# TouScruino-v1.net
KiCad netlist of a schematic drawn in EAGLE
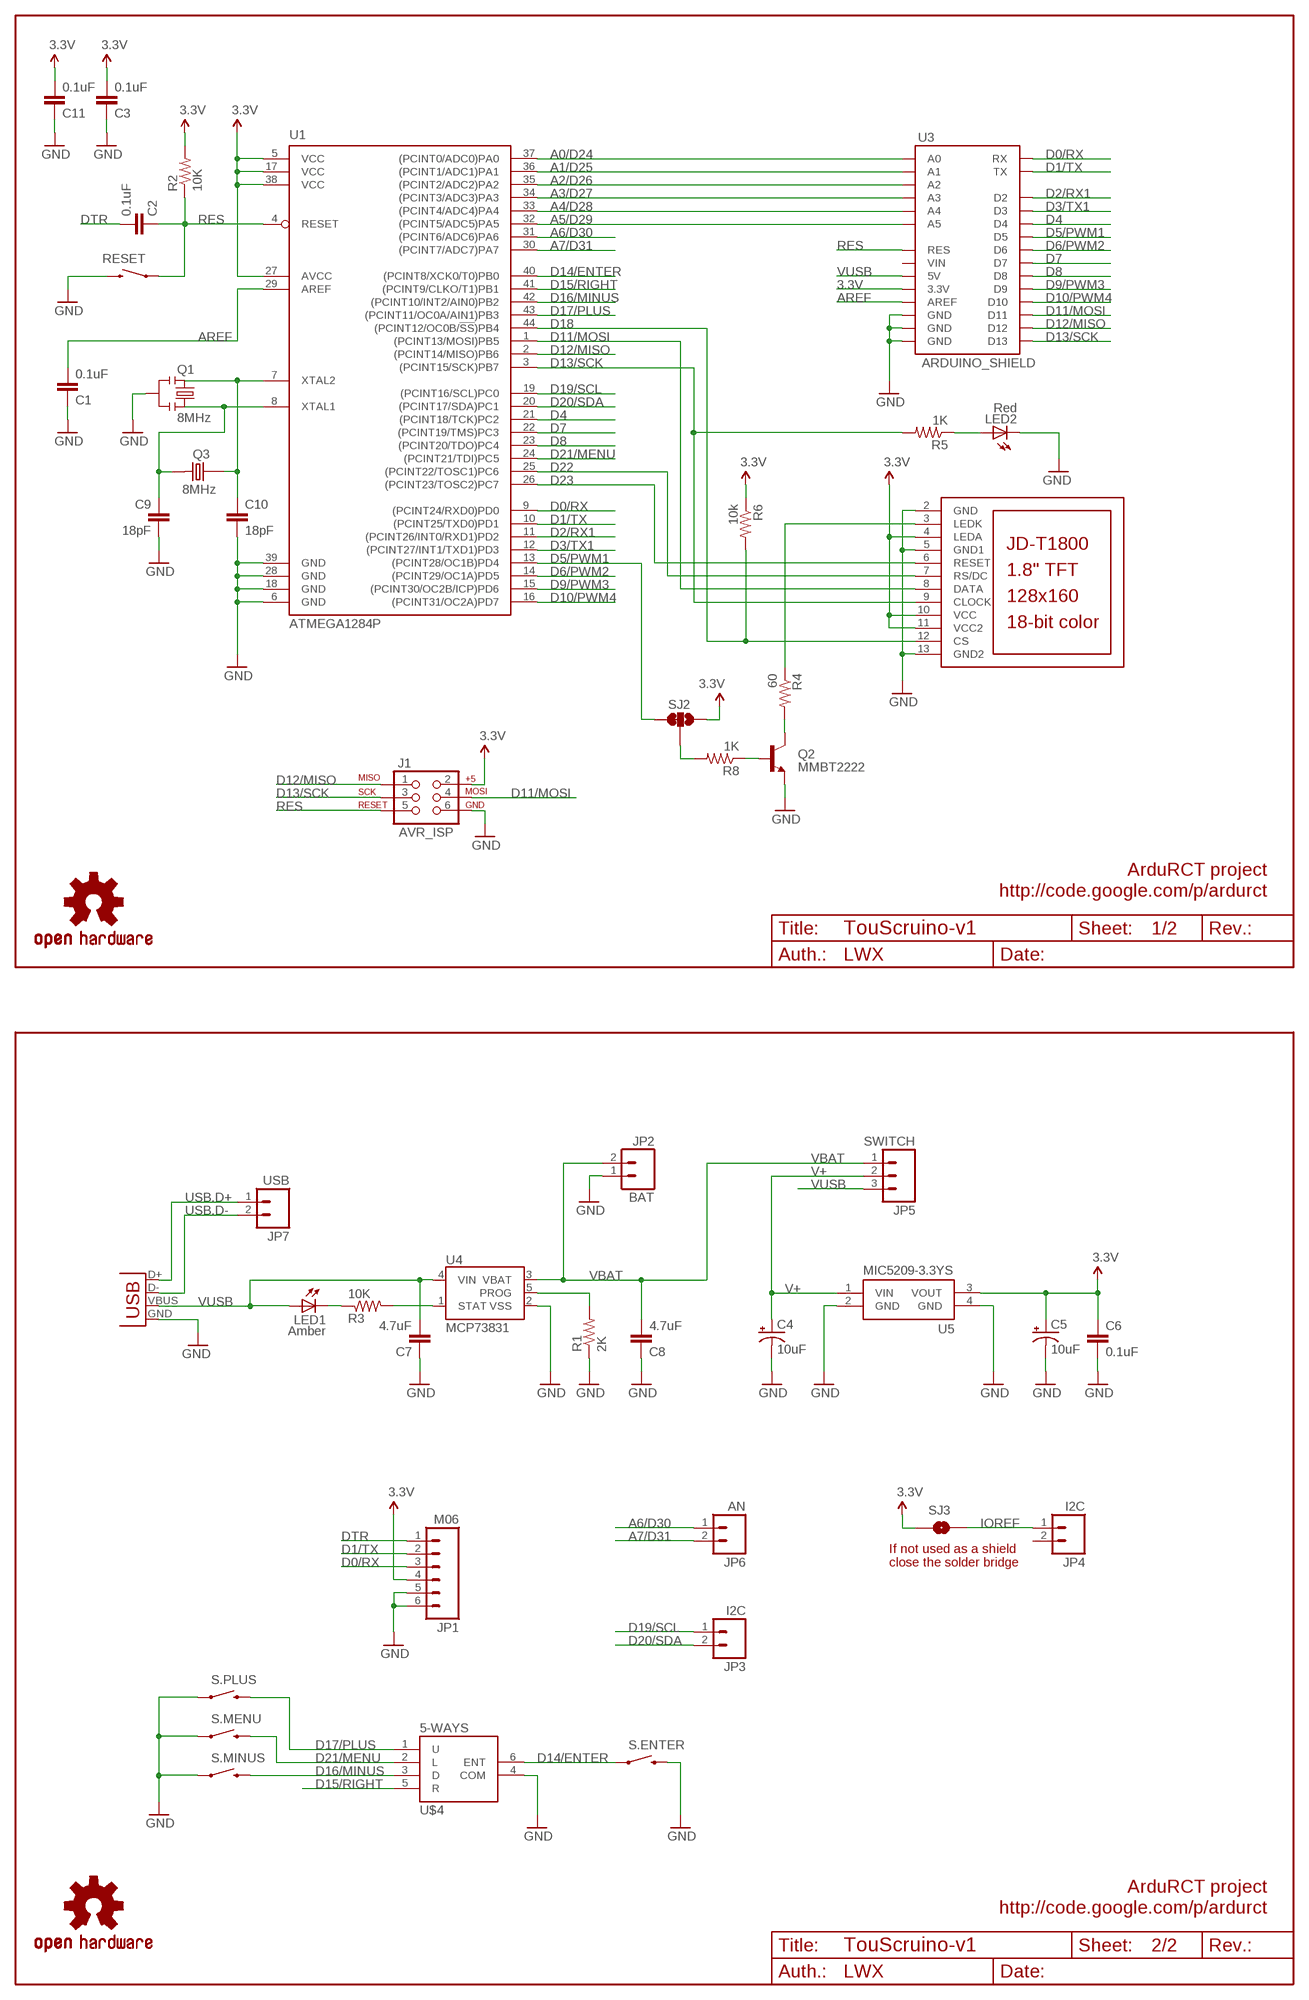
[diagram p0: schematic, sheet 1]

(export (version "E")
  (design (tool "Eeschema 10.0.6"))
  (components
    (comp (ref "C1")
      (value "0.1uF")
      (footprint "eagle-import:0805")
      (libsource (lib "eagle-import") (part "CAP0805"))
    )
    (comp (ref "C2")
      (value "0.1uF")
      (footprint "eagle-import:0805")
      (libsource (lib "eagle-import") (part "CAP0805"))
    )
    (comp (ref "C3")
      (value "0.1uF")
      (footprint "eagle-import:0805")
      (libsource (lib "eagle-import") (part "CAP0805"))
    )
    (comp (ref "C4")
      (value "10uF")
      (footprint "eagle-import:EIA3216")
      (libsource (lib "eagle-import") (part "CAP_POL1206"))
    )
    (comp (ref "C5")
      (value "10uF")
      (footprint "eagle-import:EIA3216")
      (libsource (lib "eagle-import") (part "CAP_POL1206"))
    )
    (comp (ref "C6")
      (value "0.1uF")
      (footprint "eagle-import:0805")
      (libsource (lib "eagle-import") (part "CAP0805"))
    )
    (comp (ref "C7")
      (value "4.7uF")
      (footprint "eagle-import:0805")
      (libsource (lib "eagle-import") (part "CAP0805"))
    )
    (comp (ref "C8")
      (value "4.7uF")
      (footprint "eagle-import:0805")
      (libsource (lib "eagle-import") (part "CAP0805"))
    )
    (comp (ref "C9")
      (value "18pF")
      (footprint "eagle-import:0603-CAP")
      (libsource (lib "eagle-import") (part "CAP0603-CAP"))
    )
    (comp (ref "C10")
      (value "18pF")
      (footprint "eagle-import:0603-CAP")
      (libsource (lib "eagle-import") (part "CAP0603-CAP"))
    )
    (comp (ref "C11")
      (value "0.1uF")
      (footprint "eagle-import:0805")
      (libsource (lib "eagle-import") (part "CAP0805"))
    )
    (comp (ref "J1")
      (value "AVR_ISP")
      (footprint "eagle-import:2X3")
      (libsource (lib "eagle-import") (part "AVR_SPI_PRG_6PTH"))
    )
    (comp (ref "JP1")
      (value "M06")
      (footprint "eagle-import:1X06")
      (libsource (lib "eagle-import") (part "M06"))
    )
    (comp (ref "JP2")
      (value "BAT")
      (footprint "eagle-import:JST-2-SMD")
      (libsource (lib "eagle-import") (part "M02-JST-2MM-SMT"))
    )
    (comp (ref "JP3")
      (value "I2C")
      (footprint "eagle-import:1X02")
      (libsource (lib "eagle-import") (part "M02"))
    )
    (comp (ref "JP4")
      (value "I2C")
      (footprint "eagle-import:1X02")
      (libsource (lib "eagle-import") (part "M02"))
    )
    (comp (ref "JP5")
      (value "SWITCH")
      (footprint "eagle-import:1X3_LONGPAD")
      (libsource (lib "eagle-import") (part "M03"))
    )
    (comp (ref "JP6")
      (value "AN")
      (footprint "eagle-import:1X02")
      (libsource (lib "eagle-import") (part "M02"))
    )
    (comp (ref "JP7")
      (value "USB")
      (footprint "eagle-import:1X02")
      (libsource (lib "eagle-import") (part "M02"))
    )
    (comp (ref "LCD1")
      (value "JD-T1800")
      (footprint "eagle-import:JD-T1800")
      (libsource (lib "eagle-import") (part "JD-T1800"))
    )
    (comp (ref "LED1")
      (value "Amber")
      (footprint "eagle-import:LED")
      (libsource (lib "eagle-import") (part "LED"))
    )
    (comp (ref "LED2")
      (value "Red")
      (footprint "eagle-import:LED-0805")
      (libsource (lib "eagle-import") (part "LED805"))
    )
    (comp (ref "Q1")
      (value "8MHz")
      (footprint "eagle-import:RESONATOR-SMD")
      (libsource (lib "eagle-import") (part "RESONATORSMD"))
    )
    (comp (ref "Q2")
      (value "MMBT2222")
      (footprint "eagle-import:SOT23-3")
      (libsource (lib "eagle-import") (part "TRANSISTOR_NPNSOT23-3"))
    )
    (comp (ref "Q3")
      (value "8MHz")
      (footprint "eagle-import:CRYSTAL_5X3.2")
      (libsource (lib "eagle-import") (part "CRYSTAL_5X3.2"))
    )
    (comp (ref "R1")
      (value "2K")
      (footprint "eagle-import:0805")
      (libsource (lib "eagle-import") (part "RESISTOR0805-RES"))
    )
    (comp (ref "R2")
      (value "10K")
      (footprint "eagle-import:0805")
      (libsource (lib "eagle-import") (part "RESISTOR0805-RES"))
    )
    (comp (ref "R3")
      (value "10K")
      (footprint "eagle-import:0805")
      (libsource (lib "eagle-import") (part "RESISTOR0805-RES"))
    )
    (comp (ref "R4")
      (value "60")
      (footprint "eagle-import:0805")
      (libsource (lib "eagle-import") (part "RESISTOR0805-RES"))
    )
    (comp (ref "R5")
      (value "1K")
      (footprint "eagle-import:0805")
      (libsource (lib "eagle-import") (part "RESISTOR0805-RES"))
    )
    (comp (ref "R6")
      (value "10k")
      (footprint "eagle-import:0805")
      (libsource (lib "eagle-import") (part "RESISTOR0805-RES"))
    )
    (comp (ref "R8")
      (value "1K")
      (footprint "eagle-import:0805")
      (libsource (lib "eagle-import") (part "RESISTOR0805-RES"))
    )
    (comp (ref "RESET")
      (value "SWITCH-MOMENTARY-2SMD")
      (footprint "eagle-import:TACTILE_SWITCH_SMD")
      (libsource (lib "eagle-import") (part "SWITCH-MOMENTARY-2SMD"))
    )
    (comp (ref "S.ENTER")
      (value "SWITCH_SMD")
      (footprint "eagle-import:TACTILE_SWITCH_SMD")
      (libsource (lib "eagle-import") (part "SWITCH_SMD"))
    )
    (comp (ref "S.MENU")
      (value "SWITCH_SMD")
      (footprint "eagle-import:TACTILE_SWITCH_SMD")
      (libsource (lib "eagle-import") (part "SWITCH_SMD"))
    )
    (comp (ref "S.MINUS")
      (value "SWITCH_SMD")
      (footprint "eagle-import:TACTILE_SWITCH_SMD")
      (libsource (lib "eagle-import") (part "SWITCH_SMD"))
    )
    (comp (ref "S.PLUS")
      (value "SWITCH_SMD")
      (footprint "eagle-import:TACTILE_SWITCH_SMD")
      (libsource (lib "eagle-import") (part "SWITCH_SMD"))
    )
    (comp (ref "SJ2")
      (value "SJ_2WAYS_1-2")
      (footprint "eagle-import:SJ_2WAYS_1-2_S")
      (libsource (lib "eagle-import") (part "SJ_2WAYS_1-2"))
    )
    (comp (ref "SJ3")
      (value "SOLDERJUMPERNO")
      (footprint "eagle-import:SJ_2S-NO")
      (libsource (lib "eagle-import") (part "SOLDERJUMPERNO"))
    )
    (comp (ref "U$3")
      (value "OSHW-LOGOM")
      (footprint "eagle-import:OSHW-LOGO-M")
      (libsource (lib "eagle-import") (part "OSHW-LOGOM"))
    )
    (comp (ref "U$4")
      (value "5-WAYS")
      (footprint "eagle-import:5-WAYS_ALPS")
      (libsource (lib "eagle-import") (part "5-WAYS"))
    )
    (comp (ref "U$5")
      (value "OSHW-LOGOM")
      (footprint "eagle-import:OSHW-LOGO-M")
      (libsource (lib "eagle-import") (part "OSHW-LOGOM"))
    )
    (comp (ref "U1")
      (value "ATMEGA1284P")
      (footprint "eagle-import:TQFP44")
      (libsource (lib "eagle-import") (part "ATMEGA324A"))
    )
    (comp (ref "U3")
      (value "ARDUINO_SHIELD")
      (footprint "eagle-import:ARDUINO_SHIELD")
      (libsource (lib "eagle-import") (part "ARDUINO_SHIELD"))
    )
    (comp (ref "U4")
      (value "MCP73831")
      (footprint "eagle-import:SOT23-5")
      (libsource (lib "eagle-import") (part "MCP73831"))
    )
    (comp (ref "U5")
      (value "MIC5209-3.3YS")
      (footprint "eagle-import:SOT223")
      (libsource (lib "eagle-import") (part "MIC5209"))
    )
    (comp (ref "X1")
      (value "USBSMD")
      (footprint "eagle-import:USB-MINIB")
      (libsource (lib "eagle-import") (part "USBSMD"))
    )
  )
  (nets
    (net (code "1") (name "/A0{slash}D24") (class "Default")
      (node (ref "U1") (pin "37") (pinfunction "(PCINT0/ADC0)PA0_37") (pintype "bidirectional"))
      (node (ref "U3") (pin "A0") (pinfunction "A0_A0") (pintype "bidirectional"))
    )
    (net (code "2") (name "/A1{slash}D25") (class "Default")
      (node (ref "U1") (pin "36") (pinfunction "(PCINT1/ADC1)PA1_36") (pintype "bidirectional"))
      (node (ref "U3") (pin "A1") (pinfunction "A1_A1") (pintype "bidirectional"))
    )
    (net (code "3") (name "/A2{slash}D26") (class "Default")
      (node (ref "U1") (pin "35") (pinfunction "(PCINT2/ADC2)PA2_35") (pintype "bidirectional"))
      (node (ref "U3") (pin "A2") (pinfunction "A2_A2") (pintype "bidirectional"))
    )
    (net (code "4") (name "/A3{slash}D27") (class "Default")
      (node (ref "U1") (pin "34") (pinfunction "(PCINT3/ADC3)PA3_34") (pintype "bidirectional"))
      (node (ref "U3") (pin "A3") (pinfunction "A3_A3") (pintype "bidirectional"))
    )
    (net (code "5") (name "/A4{slash}D28") (class "Default")
      (node (ref "U1") (pin "33") (pinfunction "(PCINT4/ADC4)PA4_33") (pintype "bidirectional"))
      (node (ref "U3") (pin "A4") (pinfunction "A4_A4") (pintype "bidirectional"))
    )
    (net (code "6") (name "/A5{slash}D29") (class "Default")
      (node (ref "U1") (pin "32") (pinfunction "(PCINT5/ADC5)PA5_32") (pintype "bidirectional"))
      (node (ref "U3") (pin "A5") (pinfunction "A5_A5") (pintype "bidirectional"))
    )
    (net (code "7") (name "/A6{slash}D30") (class "Default")
      (node (ref "JP6") (pin "1") (pinfunction "1_1") (pintype "passive"))
      (node (ref "U1") (pin "31") (pinfunction "(PCINT6/ADC6)PA6_31") (pintype "bidirectional"))
    )
    (net (code "8") (name "/A7{slash}D31") (class "Default")
      (node (ref "JP6") (pin "2") (pinfunction "2_2") (pintype "passive"))
      (node (ref "U1") (pin "30") (pinfunction "(PCINT7/ADC7)PA7_30") (pintype "bidirectional"))
    )
    (net (code "9") (name "/AREF") (class "Default")
      (node (ref "C1") (pin "2") (pinfunction "2_2") (pintype "passive"))
      (node (ref "U1") (pin "29") (pinfunction "AREF_29") (pintype "passive"))
      (node (ref "U3") (pin "AREF") (pinfunction "AREF_AREF") (pintype "bidirectional"))
    )
    (net (code "10") (name "/D0{slash}RX") (class "Default")
      (node (ref "JP1") (pin "3") (pinfunction "3_3") (pintype "passive"))
      (node (ref "U1") (pin "9") (pinfunction "(PCINT24/RXD0)PD0_9") (pintype "bidirectional"))
      (node (ref "U3") (pin "RX") (pinfunction "RX_RX") (pintype "bidirectional"))
    )
    (net (code "11") (name "/D1{slash}TX") (class "Default")
      (node (ref "JP1") (pin "2") (pinfunction "2_2") (pintype "passive"))
      (node (ref "U1") (pin "10") (pinfunction "(PCINT25/TXD0)PD1_10") (pintype "bidirectional"))
      (node (ref "U3") (pin "TX") (pinfunction "TX_TX") (pintype "bidirectional"))
    )
    (net (code "12") (name "/D2{slash}RX1") (class "Default")
      (node (ref "U1") (pin "11") (pinfunction "(PCINT26/INT0/RXD1)PD2_11") (pintype "bidirectional"))
      (node (ref "U3") (pin "D2") (pinfunction "D2_D2") (pintype "bidirectional"))
    )
    (net (code "13") (name "/D3{slash}TX1") (class "Default")
      (node (ref "U1") (pin "12") (pinfunction "(PCINT27/INT1/TXD1)PD3_12") (pintype "bidirectional"))
      (node (ref "U3") (pin "D3") (pinfunction "D3_D3") (pintype "bidirectional"))
    )
    (net (code "14") (name "/D4") (class "Default")
      (node (ref "U1") (pin "21") (pinfunction "(PCINT18/TCK)PC2_21") (pintype "output"))
      (node (ref "U3") (pin "D4") (pinfunction "D4_D4") (pintype "bidirectional"))
    )
    (net (code "15") (name "/D5{slash}PWM1") (class "Default")
      (node (ref "SJ2") (pin "1") (pinfunction "1_1") (pintype "passive"))
      (node (ref "U1") (pin "13") (pinfunction "(PCINT28/OC1B)PD4_13") (pintype "bidirectional"))
      (node (ref "U3") (pin "D5") (pinfunction "D5_D5") (pintype "bidirectional"))
    )
    (net (code "16") (name "/D6{slash}PWM2") (class "Default")
      (node (ref "U1") (pin "14") (pinfunction "(PCINT29/OC1A)PD5_14") (pintype "bidirectional"))
      (node (ref "U3") (pin "D6") (pinfunction "D6_D6") (pintype "bidirectional"))
    )
    (net (code "17") (name "/D7") (class "Default")
      (node (ref "U1") (pin "22") (pinfunction "(PCINT19/TMS)PC3_22") (pintype "output"))
      (node (ref "U3") (pin "D7") (pinfunction "D7_D7") (pintype "bidirectional"))
    )
    (net (code "18") (name "/D8") (class "Default")
      (node (ref "U1") (pin "23") (pinfunction "(PCINT20/TDO)PC4_23") (pintype "output"))
      (node (ref "U3") (pin "D8") (pinfunction "D8_D8") (pintype "bidirectional"))
    )
    (net (code "19") (name "/D9{slash}PWM3") (class "Default")
      (node (ref "U1") (pin "15") (pinfunction "(PCINT30/OC2B/ICP)PD6_15") (pintype "bidirectional"))
      (node (ref "U3") (pin "D9") (pinfunction "D9_D9") (pintype "bidirectional"))
    )
    (net (code "20") (name "/D10{slash}PWM4") (class "Default")
      (node (ref "U1") (pin "16") (pinfunction "(PCINT31/OC2A)PD7_16") (pintype "bidirectional"))
      (node (ref "U3") (pin "D10") (pinfunction "D10_D10") (pintype "bidirectional"))
    )
    (net (code "21") (name "/D11{slash}MOSI") (class "Default")
      (node (ref "J1") (pin "4") (pinfunction "4_4") (pintype "passive"))
      (node (ref "LCD1") (pin "8") (pinfunction "DATA_8") (pintype "bidirectional"))
      (node (ref "U1") (pin "1") (pinfunction "(PCINT13/MOSI)PB5_1") (pintype "bidirectional"))
      (node (ref "U3") (pin "D11") (pinfunction "D11_D11") (pintype "bidirectional"))
    )
    (net (code "22") (name "/D12{slash}MISO") (class "Default")
      (node (ref "J1") (pin "1") (pinfunction "1_1") (pintype "passive"))
      (node (ref "U1") (pin "2") (pinfunction "(PCINT14/MISO)PB6_2") (pintype "bidirectional"))
      (node (ref "U3") (pin "D12") (pinfunction "D12_D12") (pintype "bidirectional"))
    )
    (net (code "23") (name "/D13{slash}SCK") (class "Default")
      (node (ref "J1") (pin "3") (pinfunction "3_3") (pintype "passive"))
      (node (ref "LCD1") (pin "9") (pinfunction "CLOCK_9") (pintype "input"))
      (node (ref "R5") (pin "2") (pinfunction "2_2") (pintype "passive"))
      (node (ref "U1") (pin "3") (pinfunction "(PCINT15/SCK)PB7_3") (pintype "bidirectional"))
      (node (ref "U3") (pin "D13") (pinfunction "D13_D13") (pintype "bidirectional"))
    )
    (net (code "24") (name "/D14{slash}ENTER") (class "Default")
      (node (ref "S.ENTER") (pin "1") (pinfunction "1_1") (pintype "passive"))
      (node (ref "U$4") (pin "6") (pinfunction "ENT_6") (pintype "bidirectional"))
      (node (ref "U1") (pin "40") (pinfunction "(PCINT8/XCK0/T0)PB0_40") (pintype "bidirectional"))
    )
    (net (code "25") (name "/D15{slash}RIGHT") (class "Default")
      (node (ref "U$4") (pin "5") (pinfunction "R_5") (pintype "bidirectional"))
      (node (ref "U1") (pin "41") (pinfunction "(PCINT9/CLKO/T1)PB1_41") (pintype "bidirectional"))
    )
    (net (code "26") (name "/D16{slash}MINUS") (class "Default")
      (node (ref "S.MINUS") (pin "3") (pinfunction "2_3") (pintype "passive"))
      (node (ref "U$4") (pin "3") (pinfunction "D_3") (pintype "bidirectional"))
      (node (ref "U1") (pin "42") (pinfunction "(PCINT10/INT2/AIN0)PB2_42") (pintype "bidirectional"))
    )
    (net (code "27") (name "/D17{slash}PLUS") (class "Default")
      (node (ref "S.PLUS") (pin "3") (pinfunction "2_3") (pintype "passive"))
      (node (ref "U$4") (pin "1") (pinfunction "U_1") (pintype "bidirectional"))
      (node (ref "U1") (pin "43") (pinfunction "(PCINT11/OC0A/AIN1)PB3_43") (pintype "bidirectional"))
    )
    (net (code "28") (name "/D18") (class "Default")
      (node (ref "LCD1") (pin "12") (pinfunction "CS_12") (pintype "input"))
      (node (ref "R6") (pin "2") (pinfunction "2_2") (pintype "passive"))
      (node (ref "U1") (pin "44") (pinfunction "(PCINT12/OC0B/~{SS})PB4_44") (pintype "bidirectional"))
    )
    (net (code "29") (name "/D19{slash}SCL") (class "Default")
      (node (ref "JP3") (pin "1") (pinfunction "1_1") (pintype "passive"))
      (node (ref "U1") (pin "19") (pinfunction "(PCINT16/SCL)PC0_19") (pintype "output"))
    )
    (net (code "30") (name "/D20{slash}SDA") (class "Default")
      (node (ref "JP3") (pin "2") (pinfunction "2_2") (pintype "passive"))
      (node (ref "U1") (pin "20") (pinfunction "(PCINT17/SDA)PC1_20") (pintype "output"))
    )
    (net (code "31") (name "/D21{slash}MENU") (class "Default")
      (node (ref "S.MENU") (pin "3") (pinfunction "2_3") (pintype "passive"))
      (node (ref "U$4") (pin "2") (pinfunction "L_2") (pintype "bidirectional"))
      (node (ref "U1") (pin "24") (pinfunction "(PCINT21/TDI)PC5_24") (pintype "output"))
    )
    (net (code "32") (name "/D22") (class "Default")
      (node (ref "LCD1") (pin "7") (pinfunction "RS/DC_7") (pintype "input"))
      (node (ref "U1") (pin "25") (pinfunction "(PCINT22/TOSC1)PC6_25") (pintype "output"))
    )
    (net (code "33") (name "/D23") (class "Default")
      (node (ref "LCD1") (pin "6") (pinfunction "RESET_6") (pintype "input"))
      (node (ref "U1") (pin "26") (pinfunction "(PCINT23/TOSC2)PC7_26") (pintype "output"))
    )
    (net (code "34") (name "/DTR") (class "Default")
      (node (ref "C2") (pin "2") (pinfunction "2_2") (pintype "passive"))
      (node (ref "JP1") (pin "1") (pinfunction "1_1") (pintype "passive"))
    )
    (net (code "35") (name "/IOREF") (class "Default")
      (node (ref "JP4") (pin "1") (pinfunction "1_1") (pintype "passive"))
      (node (ref "SJ3") (pin "2") (pinfunction "2_2") (pintype "passive"))
    )
    (net (code "36") (name "/RES") (class "Default")
      (node (ref "C2") (pin "1") (pinfunction "1_1") (pintype "passive"))
      (node (ref "J1") (pin "5") (pinfunction "5_5") (pintype "passive"))
      (node (ref "R2") (pin "1") (pinfunction "1_1") (pintype "passive"))
      (node (ref "RESET") (pin "1") (pinfunction "1_1") (pintype "passive"))
      (node (ref "U1") (pin "4") (pinfunction "RESET_4") (pintype "input"))
      (node (ref "U3") (pin "RES") (pinfunction "RES_RES") (pintype "bidirectional"))
    )
    (net (code "37") (name "/USB.D+") (class "Default")
      (node (ref "JP7") (pin "1") (pinfunction "1_1") (pintype "passive"))
      (node (ref "X1") (pin "D+") (pinfunction "D+_D+") (pintype "bidirectional"))
    )
    (net (code "38") (name "/USB.D-") (class "Default")
      (node (ref "JP7") (pin "2") (pinfunction "2_2") (pintype "passive"))
      (node (ref "X1") (pin "D-") (pinfunction "D-_D-") (pintype "bidirectional"))
    )
    (net (code "39") (name "/V+") (class "Default")
      (node (ref "C4") (pin "A") (pinfunction "+_A") (pintype "passive"))
      (node (ref "JP5") (pin "2") (pinfunction "2_2") (pintype "passive"))
      (node (ref "U5") (pin "1") (pinfunction "VIN_1") (pintype "bidirectional"))
    )
    (net (code "40") (name "/VBAT") (class "Default")
      (node (ref "C8") (pin "2") (pinfunction "2_2") (pintype "passive"))
      (node (ref "JP2") (pin "2") (pinfunction "2_2") (pintype "passive"))
      (node (ref "JP5") (pin "1") (pinfunction "1_1") (pintype "passive"))
      (node (ref "U4") (pin "3") (pinfunction "VBAT_3") (pintype "power_in"))
    )
    (net (code "41") (name "/VUSB") (class "Default")
      (node (ref "C7") (pin "2") (pinfunction "2_2") (pintype "passive"))
      (node (ref "JP5") (pin "3") (pinfunction "3_3") (pintype "passive"))
      (node (ref "LED1") (pin "A1") (pinfunction "A_A1") (pintype "passive"))
      (node (ref "U3") (pin "5V") (pinfunction "5V_5V") (pintype "bidirectional"))
      (node (ref "U4") (pin "4") (pinfunction "VIN_4") (pintype "power_in"))
      (node (ref "X1") (pin "VBUS") (pinfunction "VBUS_VBUS") (pintype "bidirectional"))
    )
    (net (code "42") (name "3.3V") (class "Default")
      (node (ref "C11") (pin "2") (pinfunction "2_2") (pintype "passive"))
      (node (ref "C3") (pin "2") (pinfunction "2_2") (pintype "passive"))
      (node (ref "C5") (pin "A") (pinfunction "+_A") (pintype "passive"))
      (node (ref "C6") (pin "1") (pinfunction "1_1") (pintype "passive"))
      (node (ref "J1") (pin "2") (pinfunction "2_2") (pintype "passive"))
      (node (ref "JP1") (pin "4") (pinfunction "4_4") (pintype "passive"))
      (node (ref "LCD1") (pin "10") (pinfunction "VCC_10") (pintype "power_in"))
      (node (ref "LCD1") (pin "11") (pinfunction "VCC2_11") (pintype "power_in"))
      (node (ref "LCD1") (pin "4") (pinfunction "LEDA_4") (pintype "input"))
      (node (ref "R2") (pin "2") (pinfunction "2_2") (pintype "passive"))
      (node (ref "R6") (pin "1") (pinfunction "1_1") (pintype "passive"))
      (node (ref "SJ2") (pin "3") (pinfunction "3_3") (pintype "passive"))
      (node (ref "SJ3") (pin "1") (pinfunction "1_1") (pintype "passive"))
      (node (ref "U1") (pin "17") (pinfunction "VCC_17") (pintype "power_in"))
      (node (ref "U1") (pin "27") (pinfunction "AVCC_27") (pintype "power_in"))
      (node (ref "U1") (pin "38") (pinfunction "VCC_38") (pintype "power_in"))
      (node (ref "U1") (pin "5") (pinfunction "VCC_5") (pintype "power_in"))
      (node (ref "U3") (pin "3.3V") (pinfunction "3.3V_3.3V") (pintype "bidirectional"))
      (node (ref "U5") (pin "3") (pinfunction "VOUT_3") (pintype "bidirectional"))
    )
    (net (code "43") (name "GND") (class "Default")
      (node (ref "C1") (pin "1") (pinfunction "1_1") (pintype "passive"))
      (node (ref "C10") (pin "2") (pinfunction "2_2") (pintype "passive"))
      (node (ref "C11") (pin "1") (pinfunction "1_1") (pintype "passive"))
      (node (ref "C3") (pin "1") (pinfunction "1_1") (pintype "passive"))
      (node (ref "C4") (pin "C") (pinfunction "-_C") (pintype "passive"))
      (node (ref "C5") (pin "C") (pinfunction "-_C") (pintype "passive"))
      (node (ref "C6") (pin "2") (pinfunction "2_2") (pintype "passive"))
      (node (ref "C7") (pin "1") (pinfunction "1_1") (pintype "passive"))
      (node (ref "C8") (pin "1") (pinfunction "1_1") (pintype "passive"))
      (node (ref "C9") (pin "2") (pinfunction "2_2") (pintype "passive"))
      (node (ref "J1") (pin "6") (pinfunction "6_6") (pintype "passive"))
      (node (ref "JP1") (pin "5") (pinfunction "5_5") (pintype "passive"))
      (node (ref "JP1") (pin "6") (pinfunction "6_6") (pintype "passive"))
      (node (ref "JP2") (pin "1") (pinfunction "1_1") (pintype "passive"))
      (node (ref "LCD1") (pin "13") (pinfunction "GND2_13") (pintype "power_in"))
      (node (ref "LCD1") (pin "2") (pinfunction "GND_2") (pintype "power_in"))
      (node (ref "LCD1") (pin "5") (pinfunction "GND1_5") (pintype "power_in"))
      (node (ref "LED2") (pin "2") (pinfunction "C_2") (pintype "passive"))
      (node (ref "Q1") (pin "2") (pinfunction "2_2") (pintype "passive"))
      (node (ref "Q2") (pin "2") (pinfunction "E_2") (pintype "passive"))
      (node (ref "R1") (pin "1") (pinfunction "1_1") (pintype "passive"))
      (node (ref "RESET") (pin "3") (pinfunction "2_3") (pintype "passive"))
      (node (ref "S.ENTER") (pin "3") (pinfunction "2_3") (pintype "passive"))
      (node (ref "S.MENU") (pin "1") (pinfunction "1_1") (pintype "passive"))
      (node (ref "S.MINUS") (pin "1") (pinfunction "1_1") (pintype "passive"))
      (node (ref "S.PLUS") (pin "1") (pinfunction "1_1") (pintype "passive"))
      (node (ref "U$4") (pin "4") (pinfunction "COM_4") (pintype "bidirectional"))
      (node (ref "U1") (pin "18") (pinfunction "GND_18") (pintype "power_in"))
      (node (ref "U1") (pin "28") (pinfunction "GND_28") (pintype "power_in"))
      (node (ref "U1") (pin "39") (pinfunction "GND_39") (pintype "power_in"))
      (node (ref "U1") (pin "6") (pinfunction "GND_6") (pintype "power_in"))
      (node (ref "U3") (pin "GND@0") (pinfunction "GND_GND@0") (pintype "bidirectional"))
      (node (ref "U3") (pin "GND@1") (pinfunction "GND_GND@1") (pintype "bidirectional"))
      (node (ref "U3") (pin "GND@2") (pinfunction "GND_GND@2") (pintype "bidirectional"))
      (node (ref "U4") (pin "2") (pinfunction "VSS_2") (pintype "power_in"))
      (node (ref "U5") (pin "2") (pinfunction "GND_2") (pintype "bidirectional"))
      (node (ref "U5") (pin "4") (pinfunction "GND_4") (pintype "bidirectional"))
      (node (ref "X1") (pin "GND") (pinfunction "GND_GND") (pintype "bidirectional"))
    )
    (net (code "44") (name "Net-(LCD1-LEDK)") (class "Default")
      (node (ref "LCD1") (pin "3") (pinfunction "LEDK_3") (pintype "input"))
      (node (ref "R4") (pin "1") (pinfunction "1_1") (pintype "passive"))
    )
    (net (code "45") (name "Net-(LED1-C)") (class "Default")
      (node (ref "LED1") (pin "C1") (pinfunction "C_C1") (pintype "passive"))
      (node (ref "R3") (pin "1") (pinfunction "1_1") (pintype "passive"))
    )
    (net (code "46") (name "Net-(LED2-A)") (class "Default")
      (node (ref "LED2") (pin "1") (pinfunction "A_1") (pintype "passive"))
      (node (ref "R5") (pin "1") (pinfunction "1_1") (pintype "passive"))
    )
    (net (code "47") (name "Net-(Q2-B)") (class "Default")
      (node (ref "Q2") (pin "1") (pinfunction "B_1") (pintype "passive"))
      (node (ref "R8") (pin "1") (pinfunction "1_1") (pintype "passive"))
    )
    (net (code "48") (name "Net-(Q2-C)") (class "Default")
      (node (ref "Q2") (pin "3") (pinfunction "C_3") (pintype "passive"))
      (node (ref "R4") (pin "2") (pinfunction "2_2") (pintype "passive"))
    )
    (net (code "49") (name "Net-(R8-Pad2)") (class "Default")
      (node (ref "R8") (pin "2") (pinfunction "2_2") (pintype "passive"))
      (node (ref "SJ2") (pin "2") (pinfunction "2_2") (pintype "passive"))
    )
    (net (code "50") (name "Net-(U1-XTAL1)") (class "Default")
      (node (ref "C9") (pin "1") (pinfunction "1_1") (pintype "passive"))
      (node (ref "Q1") (pin "1") (pinfunction "1_1") (pintype "passive"))
      (node (ref "Q3") (pin "2") (pinfunction "2_2") (pintype "passive"))
      (node (ref "U1") (pin "8") (pinfunction "XTAL1_8") (pintype "bidirectional"))
    )
    (net (code "51") (name "Net-(U1-XTAL2)") (class "Default")
      (node (ref "C10") (pin "1") (pinfunction "1_1") (pintype "passive"))
      (node (ref "Q1") (pin "3") (pinfunction "3_3") (pintype "passive"))
      (node (ref "Q3") (pin "1") (pinfunction "1_1") (pintype "passive"))
      (node (ref "U1") (pin "7") (pinfunction "XTAL2_7") (pintype "bidirectional"))
    )
    (net (code "52") (name "Net-(U4-PROG)") (class "Default")
      (node (ref "R1") (pin "2") (pinfunction "2_2") (pintype "passive"))
      (node (ref "U4") (pin "5") (pinfunction "PROG_5") (pintype "input"))
    )
    (net (code "53") (name "Net-(U4-STAT)") (class "Default")
      (node (ref "R3") (pin "2") (pinfunction "2_2") (pintype "passive"))
      (node (ref "U4") (pin "1") (pinfunction "STAT_1") (pintype "output"))
    )
    (net (code "54") (name "unconnected-(JP4-Pad2)") (class "Default")
      (node (ref "JP4") (pin "2") (pinfunction "2_2") (pintype "passive"))
    )
    (net (code "55") (name "unconnected-(U3-PadVIN)") (class "Default")
      (node (ref "U3") (pin "VIN") (pinfunction "VIN_VIN") (pintype "bidirectional"))
    )
  )
)
